# Wi-Fi_Velvet_Controller.net
KiCad netlist of a schematic drawn in Altium Designer
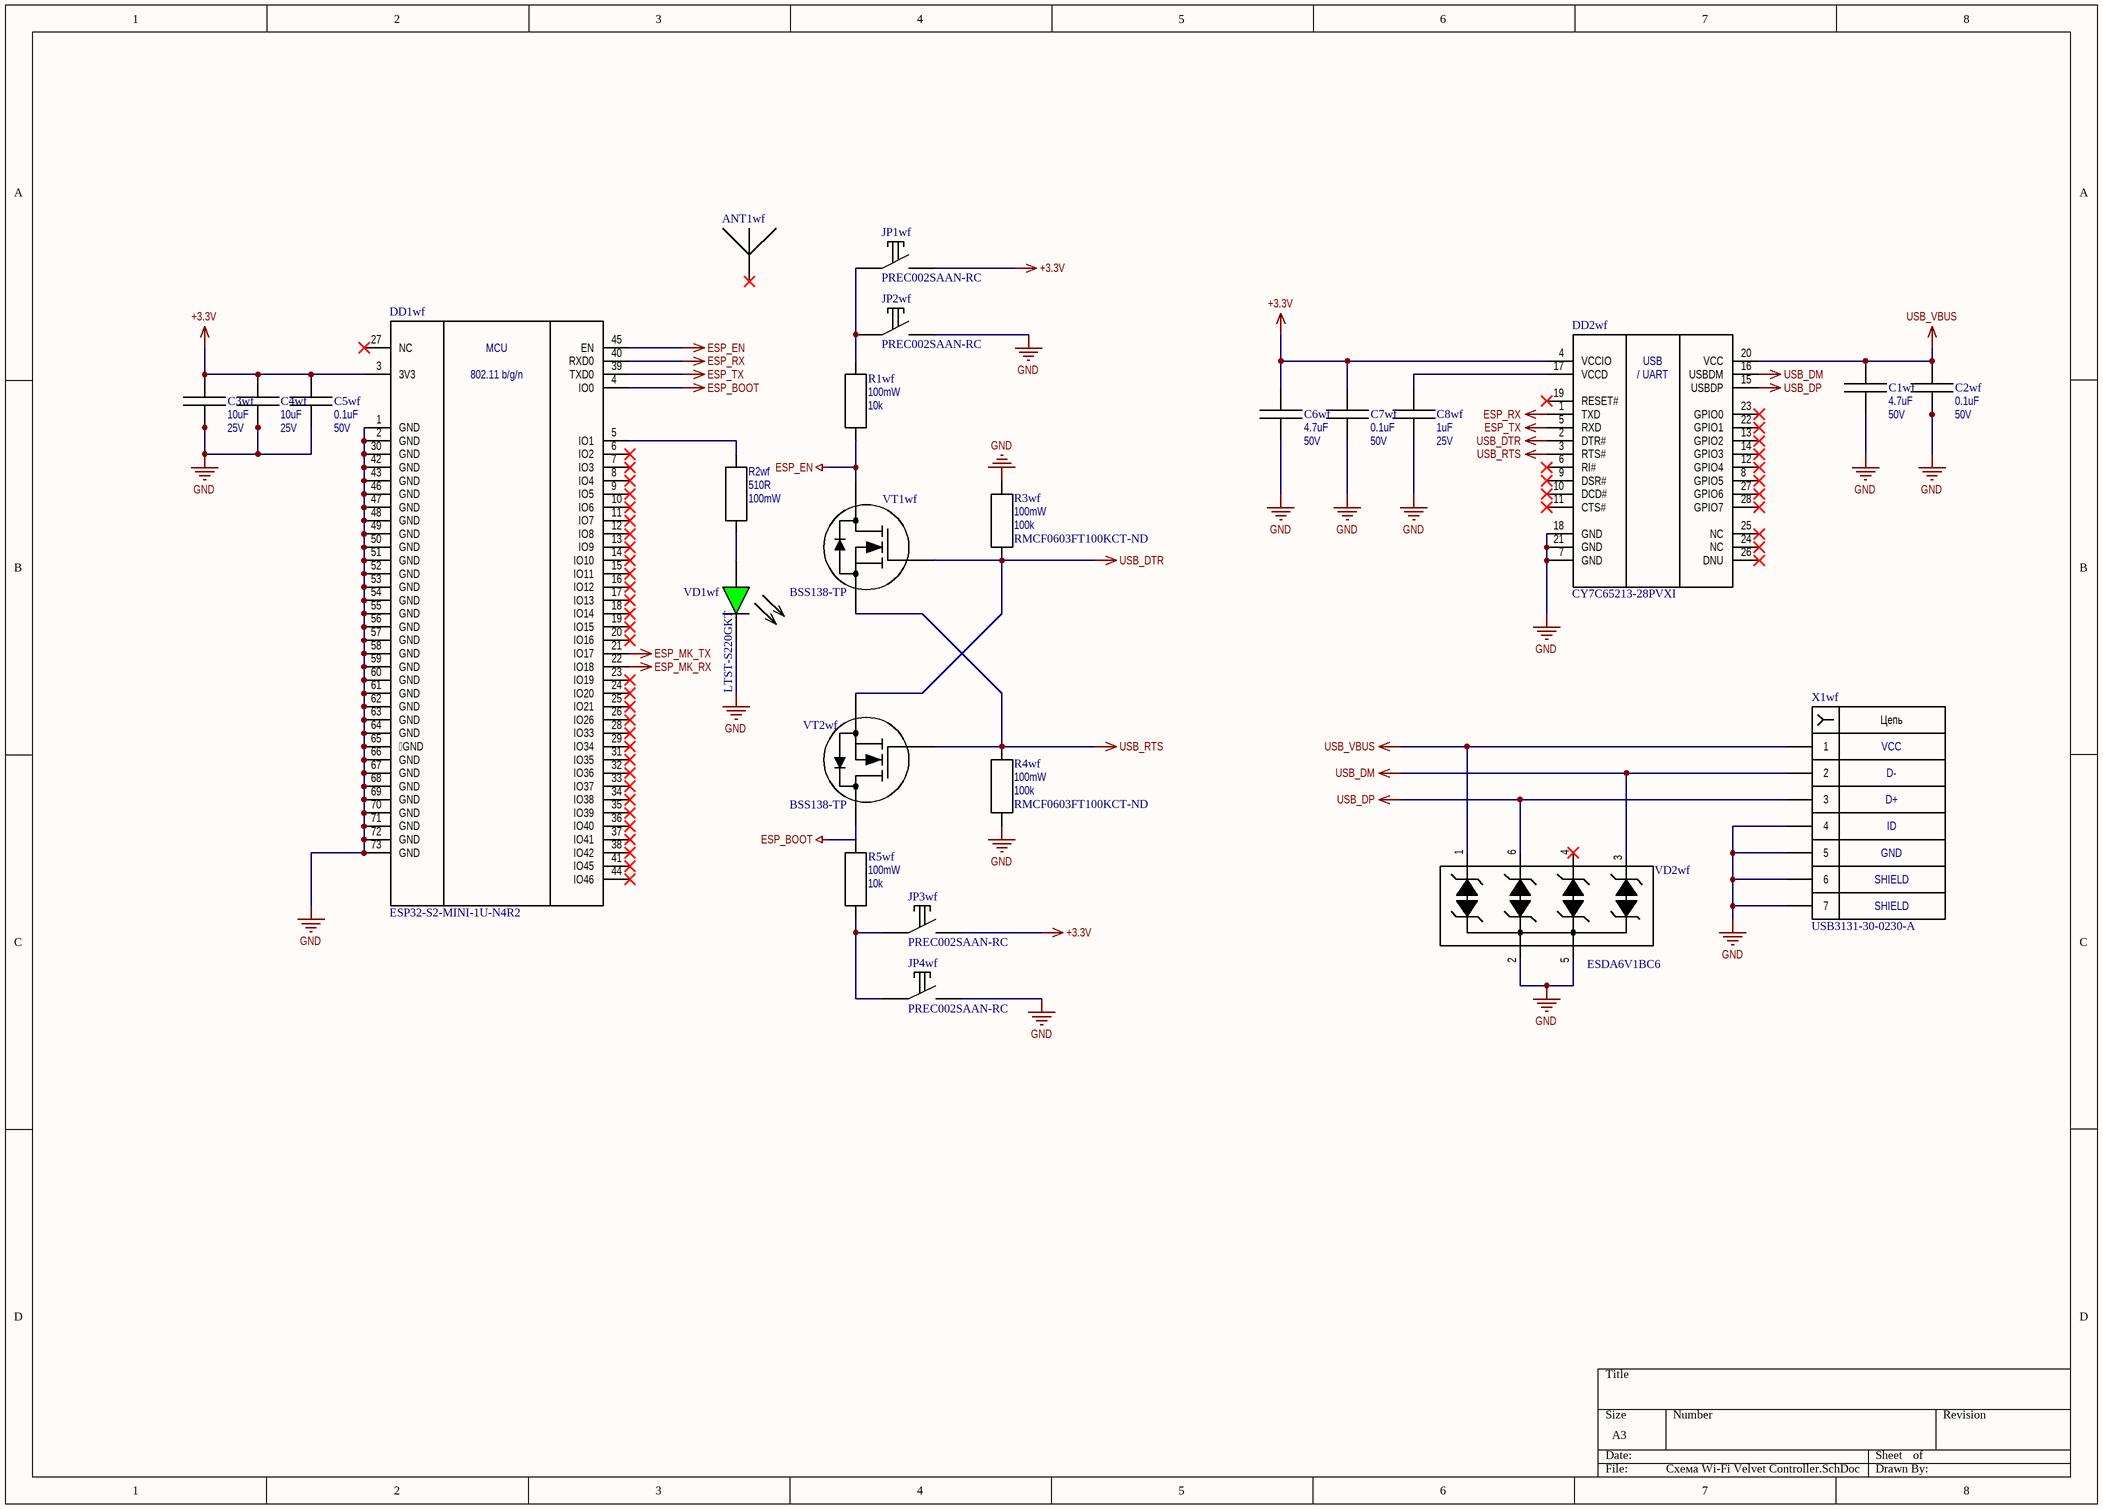
[diagram p0: Схема Wi-Fi Velvet Controller.SchDoc]

(export (version "E")
  (design (tool "Eeschema 10.0.6"))
  (components
    (comp (ref "ANT1wf")
      (value "CA-DKCA0-152L0-AJI0-O")
      (description "WATERPROOF SMA TO IPEX FOR 1.13")
      (libsource (lib "Connectors") (part "CA-DKCA0-152L0-AJI0-O"))
    )
    (comp (ref "C1wf")
      (value "CL21A475KBQNNNE")
      (footprint "CAP 0805 IPC MAX")
      (description "CAP SMD CER 4.7UF 50V X5R 0805")
      (fields
        (field (name "TOLERANCE") "10%")
        (field (name "CAPACITANCE") "4.7uF")
        (field (name "RATED VOLTAGE") "50V")
      )
      (libsource (lib "Passive components") (part "CL21A475KBQNNNE"))
    )
    (comp (ref "C2wf")
      (value "GCM188R71H104KA57D")
      (footprint "CAP 0603 IPC MAX")
      (description "CAP SMD CER 0.1UF 50V X7R 0603")
      (fields
        (field (name "TOLERANCE") "10%")
        (field (name "CAPACITANCE") "0.1uF")
        (field (name "RATED VOLTAGE") "50V")
      )
      (libsource (lib "Passive components") (part "GCM188R71H104KA57D"))
    )
    (comp (ref "C3wf")
      (value "CL31B106KAHNNNE")
      (footprint "CAP 1206 IPC MAX")
      (description "CAP SMD CER 10UF 25V X7R 1206")
      (fields
        (field (name "TOLERANCE") "10%")
        (field (name "CAPACITANCE") "10uF")
        (field (name "RATED VOLTAGE") "25V")
      )
      (libsource (lib "Passive components") (part "CL31B106KAHNNNE"))
    )
    (comp (ref "C4wf")
      (value "CL31B106KAHNNNE")
      (footprint "CAP 1206 IPC MAX")
      (description "CAP SMD CER 10UF 25V X7R 1206")
      (fields
        (field (name "TOLERANCE") "10%")
        (field (name "CAPACITANCE") "10uF")
        (field (name "RATED VOLTAGE") "25V")
      )
      (libsource (lib "Passive components") (part "CL31B106KAHNNNE"))
    )
    (comp (ref "C5wf")
      (value "GCM188R71H104KA57D")
      (footprint "CAP 0603 IPC MAX")
      (description "CAP SMD CER 0.1UF 50V X7R 0603")
      (fields
        (field (name "TOLERANCE") "10%")
        (field (name "CAPACITANCE") "0.1uF")
        (field (name "RATED VOLTAGE") "50V")
      )
      (libsource (lib "Passive components") (part "GCM188R71H104KA57D"))
    )
    (comp (ref "C6wf")
      (value "CL21A475KBQNNNE")
      (footprint "CAP 0805 IPC MAX")
      (description "CAP SMD CER 4.7UF 50V X5R 0805")
      (fields
        (field (name "TOLERANCE") "10%")
        (field (name "CAPACITANCE") "4.7uF")
        (field (name "RATED VOLTAGE") "50V")
      )
      (libsource (lib "Passive components") (part "CL21A475KBQNNNE"))
    )
    (comp (ref "C7wf")
      (value "GCM188R71H104KA57D")
      (footprint "CAP 0603 IPC MAX")
      (description "CAP SMD CER 0.1UF 50V X7R 0603")
      (fields
        (field (name "TOLERANCE") "10%")
        (field (name "CAPACITANCE") "0.1uF")
        (field (name "RATED VOLTAGE") "50V")
      )
      (libsource (lib "Passive components") (part "GCM188R71H104KA57D"))
    )
    (comp (ref "C8wf")
      (value "TMK107BJ105KA-T")
      (footprint "CAP 0603 IPC MAX")
      (description "CAP SMD CER 1UF 25V X5R 0603")
      (fields
        (field (name "TOLERANCE") "10%")
        (field (name "CAPACITANCE") "1uF")
        (field (name "RATED VOLTAGE") "25V")
      )
      (libsource (lib "Passive components") (part "TMK107BJ105KA-T"))
    )
    (comp (ref "DD1wf")
      (value "ESP32-S2-MINI-1U-N4R2")
      (footprint "ESP32­S2­MINI­1U")
      (description "SMD MODULE, ESP32-S2FN4R2 WITH WIFI 802.11B/G/N TRANCEIVER MODULE 2.4GHZ")
      (libsource (lib "Digital") (part "ESP32-S2-MINI-1U-N4R2"))
    )
    (comp (ref "DD2wf")
      (value "CY7C65213-28PVXI")
      (footprint "TSSOP-28")
      (description "IC USB-SERIAL PART 28SSOP")
      (libsource (lib "Digital") (part "CY7C65213-28PVXI"))
    )
    (comp (ref "JP1wf")
      (value "PREC002SAAN-RC")
      (footprint "2P TH 2.54mm")
      (description "CONN HEADER VERT 2POS 2.54MM")
      (libsource (lib "Connectors") (part "PREC002SAAN-RC"))
    )
    (comp (ref "JP2wf")
      (value "PREC002SAAN-RC")
      (footprint "2P TH 2.54mm")
      (description "CONN HEADER VERT 2POS 2.54MM")
      (libsource (lib "Connectors") (part "PREC002SAAN-RC"))
    )
    (comp (ref "JP3wf")
      (value "PREC002SAAN-RC")
      (footprint "2P TH 2.54mm")
      (description "CONN HEADER VERT 2POS 2.54MM")
      (libsource (lib "Connectors") (part "PREC002SAAN-RC"))
    )
    (comp (ref "JP4wf")
      (value "PREC002SAAN-RC")
      (footprint "2P TH 2.54mm")
      (description "CONN HEADER VERT 2POS 2.54MM")
      (libsource (lib "Connectors") (part "PREC002SAAN-RC"))
    )
    (comp (ref "R1wf")
      (value "RMCF0603JT10K0")
      (footprint "RES 0603 IPC MAX")
      (description "RES SMD 10K OHM 5% 1/10W 0603")
      (fields
        (field (name "TOLERANCE") "5%")
        (field (name "POWER RATED") "100mW")
        (field (name "RESISTANCE") "10k")
      )
      (libsource (lib "Passive components") (part "RMCF0603JT10K0"))
    )
    (comp (ref "R2wf")
      (value "RMCF0603JT510R")
      (footprint "RES 0603 IPC MAX")
      (description "RES 510 OHM 5% 1/10W 0603")
      (fields
        (field (name "RESISTANCE") "510R")
        (field (name "TOLERANCE") "5%")
        (field (name "POWER RATING") "100mW")
      )
      (libsource (lib "Passive components") (part "RES GOST"))
    )
    (comp (ref "R3wf")
      (value "RMCF0603FT100K")
      (footprint "RES 0603 IPC MAX")
      (description "RES SMD 100K OHM 5% 1/10W 0603")
      (fields
        (field (name "TOLERANCE") "5%")
        (field (name "POWER RATED") "100mW")
        (field (name "RESISTANCE") "100k")
        (field (name "SUPPLIER PART NUMBER 1") "RMCF0603FT100KCT-ND")
      )
      (libsource (lib "Passive components") (part "RMCF0603FT100K"))
    )
    (comp (ref "R4wf")
      (value "RMCF0603FT100K")
      (footprint "RES 0603 IPC MAX")
      (description "RES SMD 100K OHM 5% 1/10W 0603")
      (fields
        (field (name "TOLERANCE") "5%")
        (field (name "POWER RATED") "100mW")
        (field (name "RESISTANCE") "100k")
        (field (name "SUPPLIER PART NUMBER 1") "RMCF0603FT100KCT-ND")
      )
      (libsource (lib "Passive components") (part "RMCF0603FT100K"))
    )
    (comp (ref "R5wf")
      (value "RMCF0603JT10K0")
      (footprint "RES 0603 IPC MAX")
      (description "RES SMD 10K OHM 5% 1/10W 0603")
      (fields
        (field (name "TOLERANCE") "5%")
        (field (name "POWER RATED") "100mW")
        (field (name "RESISTANCE") "10k")
      )
      (libsource (lib "Passive components") (part "RMCF0603JT10K0"))
    )
    (comp (ref "VD1wf")
      (value "LTST-S220GKT")
      (footprint "0805 DIODE")
      (description "LED GREEN CLEAR SMD R/A")
      (libsource (lib "Diodes") (part "LTST-S220GKT"))
    )
    (comp (ref "VD2wf")
      (value "ESDA6V1BC6")
      (footprint "SOT-23-6")
      (description "TVS DIODE 5VWM SOT23-6")
      (libsource (lib "Diodes") (part "ESDA6V1BC6"))
    )
    (comp (ref "VT1wf")
      (value "BSS138-TP")
      (footprint "SOT-23-3")
      (description "MOSFET N-CH 50V 220MA SOT23")
      (libsource (lib "MOSFET") (part "BSS138-TP"))
    )
    (comp (ref "VT2wf")
      (value "BSS138-TP")
      (footprint "SOT-23-3")
      (description "MOSFET N-CH 50V 220MA SOT23")
      (libsource (lib "MOSFET") (part "BSS138-TP"))
    )
    (comp (ref "X1wf")
      (value "USB3131-30-0230-A")
      (footprint "USB3131-30-0230-A")
      (description "MICRO B SKT, VERTICAL, TH, 30\",")
      (libsource (lib "Connectors") (part "USB3131-30-0230-A"))
    )
  )
  (nets
    (net (code "1") (name "+3.3V") (class "Default")
      (node (ref "C3wf") (pin "1") (pinfunction "1_1") (pintype "passive"))
      (node (ref "C4wf") (pin "1") (pinfunction "1_1") (pintype "passive"))
      (node (ref "C5wf") (pin "1") (pinfunction "1_1") (pintype "passive"))
      (node (ref "C6wf") (pin "1") (pinfunction "1_1") (pintype "passive"))
      (node (ref "C7wf") (pin "1") (pinfunction "1_1") (pintype "passive"))
      (node (ref "DD1wf") (pin "3") (pinfunction "3V3_3") (pintype "passive"))
      (node (ref "DD2wf") (pin "4") (pinfunction "VCCIO_4") (pintype "passive"))
      (node (ref "JP1wf") (pin "2") (pinfunction "2_2") (pintype "passive"))
      (node (ref "JP3wf") (pin "2") (pinfunction "2_2") (pintype "passive"))
    )
    (net (code "2") (name "ESP_BOOT") (class "Default")
      (node (ref "DD1wf") (pin "4") (pinfunction "IO0_4") (pintype "passive"))
      (node (ref "R5wf") (pin "2") (pinfunction "2_2") (pintype "passive"))
      (node (ref "VT2wf") (pin "3") (pinfunction "D_3") (pintype "passive"))
    )
    (net (code "3") (name "ESP_EN") (class "Default")
      (node (ref "DD1wf") (pin "45") (pinfunction "EN_45") (pintype "passive"))
      (node (ref "R1wf") (pin "1") (pinfunction "1_1") (pintype "passive"))
      (node (ref "VT1wf") (pin "3") (pinfunction "D_3") (pintype "passive"))
    )
    (net (code "4") (name "ESP_MK_RX") (class "Default")
      (node (ref "DD1wf") (pin "22") (pinfunction "IO18_22") (pintype "passive"))
    )
    (net (code "5") (name "ESP_MK_TX") (class "Default")
      (node (ref "DD1wf") (pin "21") (pinfunction "IO17_21") (pintype "passive"))
    )
    (net (code "6") (name "ESP_RX") (class "Default")
      (node (ref "DD1wf") (pin "40") (pinfunction "RXD0_40") (pintype "passive"))
      (node (ref "DD2wf") (pin "1") (pinfunction "TXD_1") (pintype "passive"))
    )
    (net (code "7") (name "ESP_TX") (class "Default")
      (node (ref "DD1wf") (pin "39") (pinfunction "TXD0_39") (pintype "passive"))
      (node (ref "DD2wf") (pin "5") (pinfunction "RXD_5") (pintype "passive"))
    )
    (net (code "8") (name "GND") (class "Default")
      (node (ref "C1wf") (pin "2") (pinfunction "2_2") (pintype "passive"))
      (node (ref "C2wf") (pin "2") (pinfunction "2_2") (pintype "passive"))
      (node (ref "C3wf") (pin "2") (pinfunction "2_2") (pintype "passive"))
      (node (ref "C4wf") (pin "2") (pinfunction "2_2") (pintype "passive"))
      (node (ref "C5wf") (pin "2") (pinfunction "2_2") (pintype "passive"))
      (node (ref "C6wf") (pin "2") (pinfunction "2_2") (pintype "passive"))
      (node (ref "C7wf") (pin "2") (pinfunction "2_2") (pintype "passive"))
      (node (ref "C8wf") (pin "2") (pinfunction "2_2") (pintype "passive"))
      (node (ref "DD1wf") (pin "1") (pinfunction "GND_1") (pintype "passive"))
      (node (ref "DD1wf") (pin "2") (pinfunction "GND_2") (pintype "passive"))
      (node (ref "DD1wf") (pin "30") (pinfunction "GND_30") (pintype "passive"))
      (node (ref "DD1wf") (pin "42") (pinfunction "GND_42") (pintype "passive"))
      (node (ref "DD1wf") (pin "43") (pinfunction "GND_43") (pintype "passive"))
      (node (ref "DD1wf") (pin "46") (pinfunction "GND_46") (pintype "passive"))
      (node (ref "DD1wf") (pin "47") (pinfunction "GND_47") (pintype "passive"))
      (node (ref "DD1wf") (pin "48") (pinfunction "GND_48") (pintype "passive"))
      (node (ref "DD1wf") (pin "49") (pinfunction "GND_49") (pintype "passive"))
      (node (ref "DD1wf") (pin "50") (pinfunction "GND_50") (pintype "passive"))
      (node (ref "DD1wf") (pin "51") (pinfunction "GND_51") (pintype "passive"))
      (node (ref "DD1wf") (pin "52") (pinfunction "GND_52") (pintype "passive"))
      (node (ref "DD1wf") (pin "53") (pinfunction "GND_53") (pintype "passive"))
      (node (ref "DD1wf") (pin "54") (pinfunction "GND_54") (pintype "passive"))
      (node (ref "DD1wf") (pin "55") (pinfunction "GND_55") (pintype "passive"))
      (node (ref "DD1wf") (pin "56") (pinfunction "GND_56") (pintype "passive"))
      (node (ref "DD1wf") (pin "57") (pinfunction "GND_57") (pintype "passive"))
      (node (ref "DD1wf") (pin "58") (pinfunction "GND_58") (pintype "passive"))
      (node (ref "DD1wf") (pin "59") (pinfunction "GND_59") (pintype "passive"))
      (node (ref "DD1wf") (pin "60") (pinfunction "GND_60") (pintype "passive"))
      (node (ref "DD1wf") (pin "61") (pinfunction "GND_61") (pintype "passive"))
      (node (ref "DD1wf") (pin "62") (pinfunction "GND_62") (pintype "passive"))
      (node (ref "DD1wf") (pin "63") (pinfunction "GND_63") (pintype "passive"))
      (node (ref "DD1wf") (pin "64") (pinfunction "GND_64") (pintype "passive"))
      (node (ref "DD1wf") (pin "65") (pinfunction "GND_65") (pintype "passive"))
      (node (ref "DD1wf") (pin "66") (pinfunction "GND_66") (pintype "passive"))
      (node (ref "DD1wf") (pin "67") (pinfunction "GND_67") (pintype "passive"))
      (node (ref "DD1wf") (pin "68") (pinfunction "GND_68") (pintype "passive"))
      (node (ref "DD1wf") (pin "69") (pinfunction "GND_69") (pintype "passive"))
      (node (ref "DD1wf") (pin "70") (pinfunction "GND_70") (pintype "passive"))
      (node (ref "DD1wf") (pin "71") (pinfunction "GND_71") (pintype "passive"))
      (node (ref "DD1wf") (pin "72") (pinfunction "GND_72") (pintype "passive"))
      (node (ref "DD1wf") (pin "73") (pinfunction "GND_73") (pintype "passive"))
      (node (ref "DD2wf") (pin "18") (pinfunction "GND_18") (pintype "passive"))
      (node (ref "DD2wf") (pin "21") (pinfunction "GND_21") (pintype "passive"))
      (node (ref "DD2wf") (pin "7") (pinfunction "GND_7") (pintype "passive"))
      (node (ref "JP2wf") (pin "2") (pinfunction "2_2") (pintype "passive"))
      (node (ref "JP4wf") (pin "2") (pinfunction "2_2") (pintype "passive"))
      (node (ref "R3wf") (pin "2") (pinfunction "2_2") (pintype "passive"))
      (node (ref "R4wf") (pin "1") (pinfunction "1_1") (pintype "passive"))
      (node (ref "VD1wf") (pin "2") (pinfunction "2_2") (pintype "passive"))
      (node (ref "VD2wf") (pin "2") (pinfunction "2_2") (pintype "passive"))
      (node (ref "VD2wf") (pin "5") (pinfunction "5_5") (pintype "passive"))
      (node (ref "X1wf") (pin "4") (pinfunction "4_4") (pintype "passive"))
      (node (ref "X1wf") (pin "5") (pinfunction "5_5") (pintype "passive"))
      (node (ref "X1wf") (pin "6") (pinfunction "6_6") (pintype "passive"))
      (node (ref "X1wf") (pin "7") (pinfunction "7_7") (pintype "passive"))
    )
    (net (code "9") (name "Net-(DD1wf-IO1)") (class "Default")
      (node (ref "DD1wf") (pin "5") (pinfunction "IO1_5") (pintype "passive"))
      (node (ref "R2wf") (pin "1") (pinfunction "1_1") (pintype "passive"))
    )
    (net (code "10") (name "Net-(DD2wf-VCCD)") (class "Default")
      (node (ref "C8wf") (pin "1") (pinfunction "1_1") (pintype "passive"))
      (node (ref "DD2wf") (pin "17") (pinfunction "VCCD_17") (pintype "passive"))
    )
    (net (code "11") (name "Net-(JP1wf-Pad1)") (class "Default")
      (node (ref "JP1wf") (pin "1") (pinfunction "1_1") (pintype "passive"))
      (node (ref "JP2wf") (pin "1") (pinfunction "1_1") (pintype "passive"))
      (node (ref "R1wf") (pin "2") (pinfunction "2_2") (pintype "passive"))
    )
    (net (code "12") (name "Net-(JP3wf-Pad1)") (class "Default")
      (node (ref "JP3wf") (pin "1") (pinfunction "1_1") (pintype "passive"))
      (node (ref "JP4wf") (pin "1") (pinfunction "1_1") (pintype "passive"))
      (node (ref "R5wf") (pin "1") (pinfunction "1_1") (pintype "passive"))
    )
    (net (code "13") (name "Net-(R2wf-Pad2)") (class "Default")
      (node (ref "R2wf") (pin "2") (pinfunction "2_2") (pintype "passive"))
      (node (ref "VD1wf") (pin "1") (pinfunction "1_1") (pintype "passive"))
    )
    (net (code "14") (name "USB_DM") (class "Default")
      (node (ref "DD2wf") (pin "16") (pinfunction "USBDM_16") (pintype "passive"))
      (node (ref "VD2wf") (pin "3") (pinfunction "3_3") (pintype "passive"))
      (node (ref "X1wf") (pin "2") (pinfunction "2_2") (pintype "passive"))
    )
    (net (code "15") (name "USB_DP") (class "Default")
      (node (ref "DD2wf") (pin "15") (pinfunction "USBDP_15") (pintype "passive"))
      (node (ref "VD2wf") (pin "6") (pinfunction "6_6") (pintype "passive"))
      (node (ref "X1wf") (pin "3") (pinfunction "3_3") (pintype "passive"))
    )
    (net (code "16") (name "USB_DTR") (class "Default")
      (node (ref "DD2wf") (pin "2") (pinfunction "DTR#_2") (pintype "passive"))
      (node (ref "R3wf") (pin "1") (pinfunction "1_1") (pintype "passive"))
      (node (ref "VT1wf") (pin "1") (pinfunction "G_1") (pintype "passive"))
      (node (ref "VT2wf") (pin "2") (pinfunction "S_2") (pintype "passive"))
    )
    (net (code "17") (name "USB_RTS") (class "Default")
      (node (ref "DD2wf") (pin "3") (pinfunction "RTS#_3") (pintype "passive"))
      (node (ref "R4wf") (pin "2") (pinfunction "2_2") (pintype "passive"))
      (node (ref "VT1wf") (pin "2") (pinfunction "S_2") (pintype "passive"))
      (node (ref "VT2wf") (pin "1") (pinfunction "G_1") (pintype "passive"))
    )
    (net (code "18") (name "USB_VBUS") (class "Default")
      (node (ref "C1wf") (pin "1") (pinfunction "1_1") (pintype "passive"))
      (node (ref "C2wf") (pin "1") (pinfunction "1_1") (pintype "passive"))
      (node (ref "DD2wf") (pin "20") (pinfunction "VCC_20") (pintype "passive"))
      (node (ref "VD2wf") (pin "1") (pinfunction "1_1") (pintype "passive"))
      (node (ref "X1wf") (pin "1") (pinfunction "1_1") (pintype "passive"))
    )
    (net (code "19") (name "unconnected-(ANT1wf-Pad1)") (class "Default")
      (node (ref "ANT1wf") (pin "1") (pinfunction "1_1") (pintype "passive+no_connect"))
    )
    (net (code "20") (name "unconnected-(DD1wf-IO2-Pad6)") (class "Default")
      (node (ref "DD1wf") (pin "6") (pinfunction "IO2_6") (pintype "passive+no_connect"))
    )
    (net (code "21") (name "unconnected-(DD1wf-IO3-Pad7)") (class "Default")
      (node (ref "DD1wf") (pin "7") (pinfunction "IO3_7") (pintype "passive+no_connect"))
    )
    (net (code "22") (name "unconnected-(DD1wf-IO4-Pad8)") (class "Default")
      (node (ref "DD1wf") (pin "8") (pinfunction "IO4_8") (pintype "passive+no_connect"))
    )
    (net (code "23") (name "unconnected-(DD1wf-IO5-Pad9)") (class "Default")
      (node (ref "DD1wf") (pin "9") (pinfunction "IO5_9") (pintype "passive+no_connect"))
    )
    (net (code "24") (name "unconnected-(DD1wf-IO6-Pad10)") (class "Default")
      (node (ref "DD1wf") (pin "10") (pinfunction "IO6_10") (pintype "passive+no_connect"))
    )
    (net (code "25") (name "unconnected-(DD1wf-IO7-Pad11)") (class "Default")
      (node (ref "DD1wf") (pin "11") (pinfunction "IO7_11") (pintype "passive+no_connect"))
    )
    (net (code "26") (name "unconnected-(DD1wf-IO8-Pad12)") (class "Default")
      (node (ref "DD1wf") (pin "12") (pinfunction "IO8_12") (pintype "passive+no_connect"))
    )
    (net (code "27") (name "unconnected-(DD1wf-IO9-Pad13)") (class "Default")
      (node (ref "DD1wf") (pin "13") (pinfunction "IO9_13") (pintype "passive+no_connect"))
    )
    (net (code "28") (name "unconnected-(DD1wf-IO10-Pad14)") (class "Default")
      (node (ref "DD1wf") (pin "14") (pinfunction "IO10_14") (pintype "passive+no_connect"))
    )
    (net (code "29") (name "unconnected-(DD1wf-IO11-Pad15)") (class "Default")
      (node (ref "DD1wf") (pin "15") (pinfunction "IO11_15") (pintype "passive+no_connect"))
    )
    (net (code "30") (name "unconnected-(DD1wf-IO12-Pad16)") (class "Default")
      (node (ref "DD1wf") (pin "16") (pinfunction "IO12_16") (pintype "passive+no_connect"))
    )
    (net (code "31") (name "unconnected-(DD1wf-IO13-Pad17)") (class "Default")
      (node (ref "DD1wf") (pin "17") (pinfunction "IO13_17") (pintype "passive+no_connect"))
    )
    (net (code "32") (name "unconnected-(DD1wf-IO14-Pad18)") (class "Default")
      (node (ref "DD1wf") (pin "18") (pinfunction "IO14_18") (pintype "passive+no_connect"))
    )
    (net (code "33") (name "unconnected-(DD1wf-IO15-Pad19)") (class "Default")
      (node (ref "DD1wf") (pin "19") (pinfunction "IO15_19") (pintype "passive+no_connect"))
    )
    (net (code "34") (name "unconnected-(DD1wf-IO16-Pad20)") (class "Default")
      (node (ref "DD1wf") (pin "20") (pinfunction "IO16_20") (pintype "passive+no_connect"))
    )
    (net (code "35") (name "unconnected-(DD1wf-IO19-Pad23)") (class "Default")
      (node (ref "DD1wf") (pin "23") (pinfunction "IO19_23") (pintype "passive+no_connect"))
    )
    (net (code "36") (name "unconnected-(DD1wf-IO20-Pad24)") (class "Default")
      (node (ref "DD1wf") (pin "24") (pinfunction "IO20_24") (pintype "passive+no_connect"))
    )
    (net (code "37") (name "unconnected-(DD1wf-IO21-Pad25)") (class "Default")
      (node (ref "DD1wf") (pin "25") (pinfunction "IO21_25") (pintype "passive+no_connect"))
    )
    (net (code "38") (name "unconnected-(DD1wf-IO26-Pad26)") (class "Default")
      (node (ref "DD1wf") (pin "26") (pinfunction "IO26_26") (pintype "passive+no_connect"))
    )
    (net (code "39") (name "unconnected-(DD1wf-IO33-Pad28)") (class "Default")
      (node (ref "DD1wf") (pin "28") (pinfunction "IO33_28") (pintype "passive+no_connect"))
    )
    (net (code "40") (name "unconnected-(DD1wf-IO34-Pad29)") (class "Default")
      (node (ref "DD1wf") (pin "29") (pinfunction "IO34_29") (pintype "passive+no_connect"))
    )
    (net (code "41") (name "unconnected-(DD1wf-IO35-Pad31)") (class "Default")
      (node (ref "DD1wf") (pin "31") (pinfunction "IO35_31") (pintype "passive+no_connect"))
    )
    (net (code "42") (name "unconnected-(DD1wf-IO36-Pad32)") (class "Default")
      (node (ref "DD1wf") (pin "32") (pinfunction "IO36_32") (pintype "passive+no_connect"))
    )
    (net (code "43") (name "unconnected-(DD1wf-IO37-Pad33)") (class "Default")
      (node (ref "DD1wf") (pin "33") (pinfunction "IO37_33") (pintype "passive+no_connect"))
    )
    (net (code "44") (name "unconnected-(DD1wf-IO38-Pad34)") (class "Default")
      (node (ref "DD1wf") (pin "34") (pinfunction "IO38_34") (pintype "passive+no_connect"))
    )
    (net (code "45") (name "unconnected-(DD1wf-IO39-Pad35)") (class "Default")
      (node (ref "DD1wf") (pin "35") (pinfunction "IO39_35") (pintype "passive+no_connect"))
    )
    (net (code "46") (name "unconnected-(DD1wf-IO40-Pad36)") (class "Default")
      (node (ref "DD1wf") (pin "36") (pinfunction "IO40_36") (pintype "passive+no_connect"))
    )
    (net (code "47") (name "unconnected-(DD1wf-IO41-Pad37)") (class "Default")
      (node (ref "DD1wf") (pin "37") (pinfunction "IO41_37") (pintype "passive+no_connect"))
    )
    (net (code "48") (name "unconnected-(DD1wf-IO42-Pad38)") (class "Default")
      (node (ref "DD1wf") (pin "38") (pinfunction "IO42_38") (pintype "passive+no_connect"))
    )
    (net (code "49") (name "unconnected-(DD1wf-IO45-Pad41)") (class "Default")
      (node (ref "DD1wf") (pin "41") (pinfunction "IO45_41") (pintype "passive+no_connect"))
    )
    (net (code "50") (name "unconnected-(DD1wf-IO46-Pad44)") (class "Default")
      (node (ref "DD1wf") (pin "44") (pinfunction "IO46_44") (pintype "passive+no_connect"))
    )
    (net (code "51") (name "unconnected-(DD1wf-NC-Pad27)") (class "Default")
      (node (ref "DD1wf") (pin "27") (pinfunction "NC_27") (pintype "passive+no_connect"))
    )
    (net (code "52") (name "unconnected-(DD2wf-CTS#-Pad11)") (class "Default")
      (node (ref "DD2wf") (pin "11") (pinfunction "CTS#_11") (pintype "passive+no_connect"))
    )
    (net (code "53") (name "unconnected-(DD2wf-DCD#-Pad10)") (class "Default")
      (node (ref "DD2wf") (pin "10") (pinfunction "DCD#_10") (pintype "passive+no_connect"))
    )
    (net (code "54") (name "unconnected-(DD2wf-DNU-Pad26)") (class "Default")
      (node (ref "DD2wf") (pin "26") (pinfunction "DNU_26") (pintype "passive+no_connect"))
    )
    (net (code "55") (name "unconnected-(DD2wf-DSR#-Pad9)") (class "Default")
      (node (ref "DD2wf") (pin "9") (pinfunction "DSR#_9") (pintype "passive+no_connect"))
    )
    (net (code "56") (name "unconnected-(DD2wf-GPIO0-Pad23)") (class "Default")
      (node (ref "DD2wf") (pin "23") (pinfunction "GPIO0_23") (pintype "passive+no_connect"))
    )
    (net (code "57") (name "unconnected-(DD2wf-GPIO1-Pad22)") (class "Default")
      (node (ref "DD2wf") (pin "22") (pinfunction "GPIO1_22") (pintype "passive+no_connect"))
    )
    (net (code "58") (name "unconnected-(DD2wf-GPIO2-Pad13)") (class "Default")
      (node (ref "DD2wf") (pin "13") (pinfunction "GPIO2_13") (pintype "passive+no_connect"))
    )
    (net (code "59") (name "unconnected-(DD2wf-GPIO3-Pad14)") (class "Default")
      (node (ref "DD2wf") (pin "14") (pinfunction "GPIO3_14") (pintype "passive+no_connect"))
    )
    (net (code "60") (name "unconnected-(DD2wf-GPIO4-Pad12)") (class "Default")
      (node (ref "DD2wf") (pin "12") (pinfunction "GPIO4_12") (pintype "passive+no_connect"))
    )
    (net (code "61") (name "unconnected-(DD2wf-GPIO5-Pad8)") (class "Default")
      (node (ref "DD2wf") (pin "8") (pinfunction "GPIO5_8") (pintype "passive+no_connect"))
    )
    (net (code "62") (name "unconnected-(DD2wf-GPIO6-Pad27)") (class "Default")
      (node (ref "DD2wf") (pin "27") (pinfunction "GPIO6_27") (pintype "passive+no_connect"))
    )
    (net (code "63") (name "unconnected-(DD2wf-GPIO7-Pad28)") (class "Default")
      (node (ref "DD2wf") (pin "28") (pinfunction "GPIO7_28") (pintype "passive+no_connect"))
    )
    (net (code "64") (name "unconnected-(DD2wf-NC-Pad24)") (class "Default")
      (node (ref "DD2wf") (pin "24") (pinfunction "NC_24") (pintype "passive+no_connect"))
    )
    (net (code "65") (name "unconnected-(DD2wf-NC-Pad25)") (class "Default")
      (node (ref "DD2wf") (pin "25") (pinfunction "NC_25") (pintype "passive+no_connect"))
    )
    (net (code "66") (name "unconnected-(DD2wf-RESET#-Pad19)") (class "Default")
      (node (ref "DD2wf") (pin "19") (pinfunction "RESET#_19") (pintype "passive+no_connect"))
    )
    (net (code "67") (name "unconnected-(DD2wf-RI#-Pad6)") (class "Default")
      (node (ref "DD2wf") (pin "6") (pinfunction "RI#_6") (pintype "passive+no_connect"))
    )
    (net (code "68") (name "unconnected-(VD2wf-Pad4)") (class "Default")
      (node (ref "VD2wf") (pin "4") (pinfunction "4_4") (pintype "passive+no_connect"))
    )
  )
)
